# SCH_laser-read-ldr_2022-01-18.net
KiCad netlist of a schematic drawn in EasyEDA
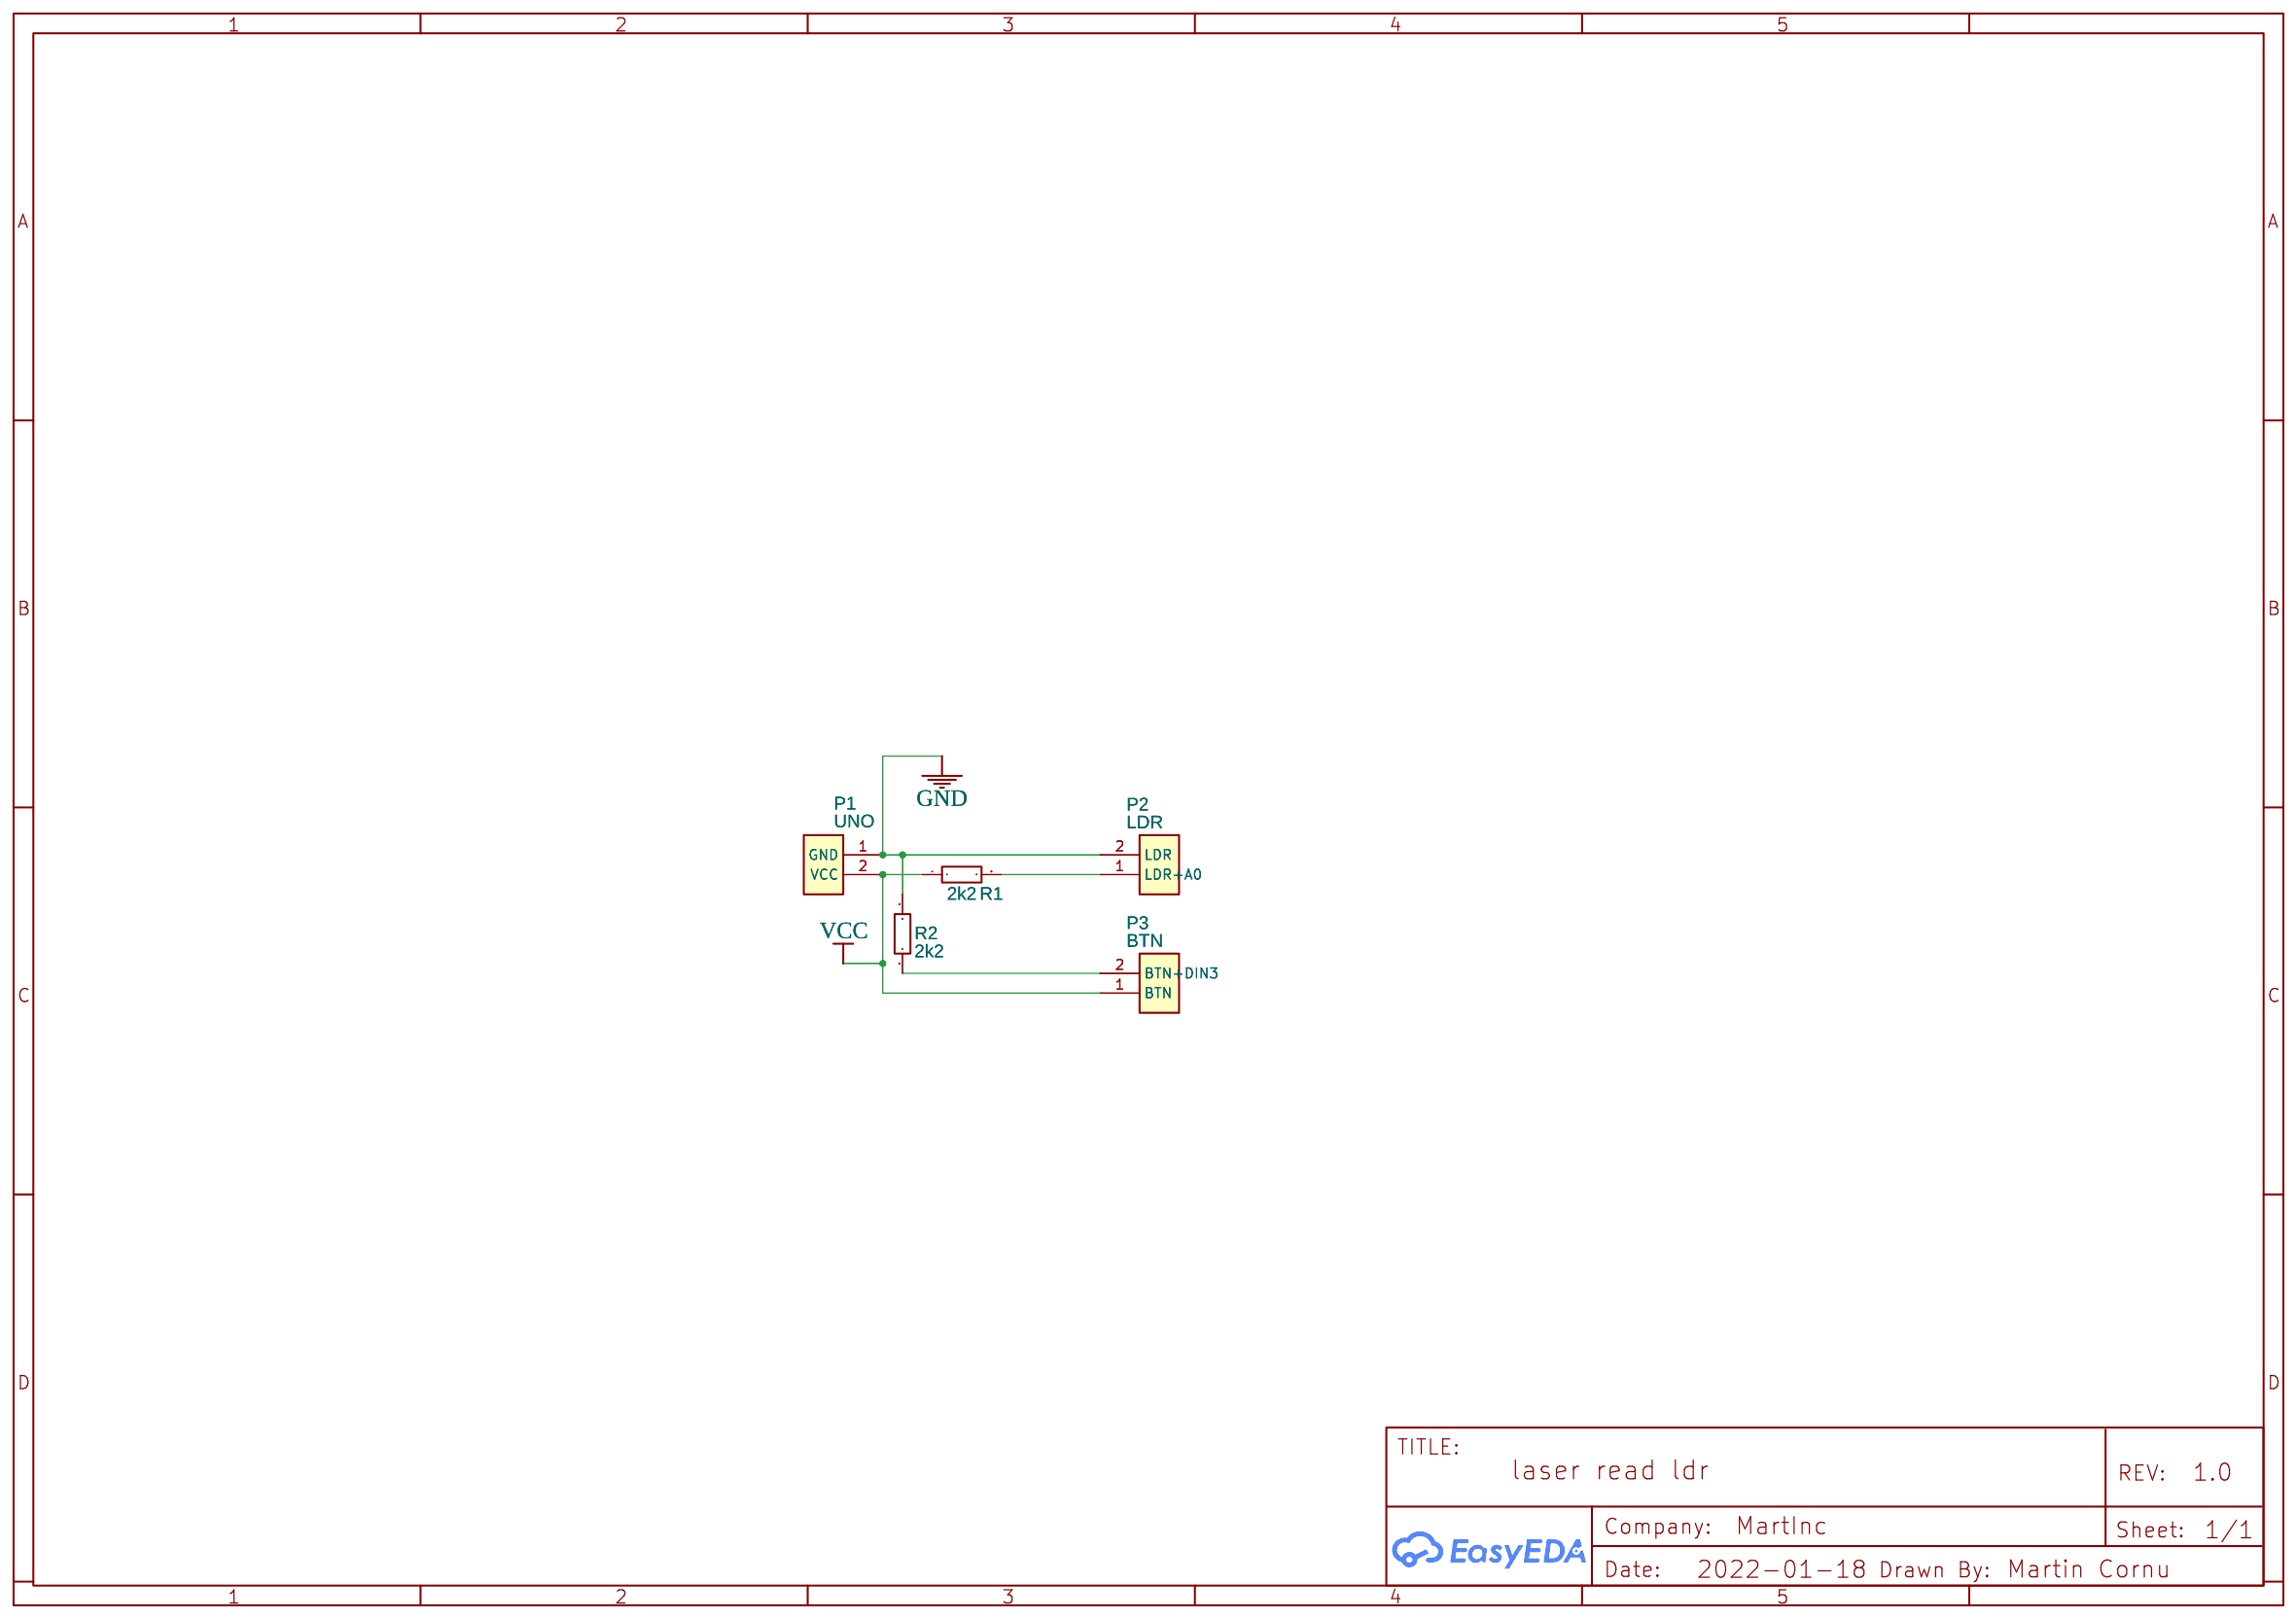
[diagram p0: schematic sheet]

(export (version "E")
  (design (tool "Eeschema 10.0.6"))
  (components
    (comp (ref "P1")
      (value "UNO")
      (fields (field (name "BOM_Supplier Part") "undefined"))
      (libsource (lib "") (part "TERMINAL_2P_5MM_2"))
    )
    (comp (ref "P2")
      (value "LDR")
      (fields (field (name "BOM_Supplier Part") "undefined"))
      (libsource (lib "") (part "TERMINAL_2P_5MM"))
    )
    (comp (ref "P3")
      (value "BTN")
      (fields (field (name "BOM_Supplier Part") "undefined"))
      (libsource (lib "") (part "TERMINAL_2P_5MM_1"))
    )
    (comp (ref "R1")
      (value "2k2")
      (fields
        (field (name "BOM_Manufacturer Part") "EWWR0001J20R0T9")
        (field (name "BOM_Supplier Part") "C348838")
      )
      (libsource (lib "") (part "Resistor2m"))
    )
    (comp (ref "R2")
      (value "2k2")
      (fields
        (field (name "BOM_Manufacturer Part") "EWWR0001J20R0T9")
        (field (name "BOM_Supplier Part") "C348838")
      )
      (libsource (lib "") (part "Resistor2m_1"))
    )
  )
  (nets
    (net (code "1") (name "GND") (class "Default")
      (node (ref "P1") (pin "1") (pinfunction "GND_1") (pintype "unspecified"))
      (node (ref "P2") (pin "2") (pinfunction "LDR_2") (pintype "unspecified"))
      (node (ref "R2") (pin "2") (pinfunction "2_2") (pintype "unspecified"))
    )
    (net (code "2") (name "Net-(P2-LDR+A0)") (class "Default")
      (node (ref "P2") (pin "1") (pinfunction "LDR+A0_1") (pintype "unspecified"))
      (node (ref "R1") (pin "2") (pinfunction "2_2") (pintype "unspecified"))
    )
    (net (code "3") (name "Net-(P3-BTN+DIN3)") (class "Default")
      (node (ref "P3") (pin "2") (pinfunction "BTN+DIN3_2") (pintype "unspecified"))
      (node (ref "R2") (pin "1") (pinfunction "1_1") (pintype "unspecified"))
    )
    (net (code "4") (name "VCC") (class "Default")
      (node (ref "P1") (pin "2") (pinfunction "VCC_2") (pintype "unspecified"))
      (node (ref "P3") (pin "1") (pinfunction "BTN_1") (pintype "unspecified"))
      (node (ref "R1") (pin "1") (pinfunction "1_1") (pintype "unspecified"))
    )
  )
)
